# CPU_Dev_revB_2.net
KiCad netlist of a schematic drawn in EAGLE
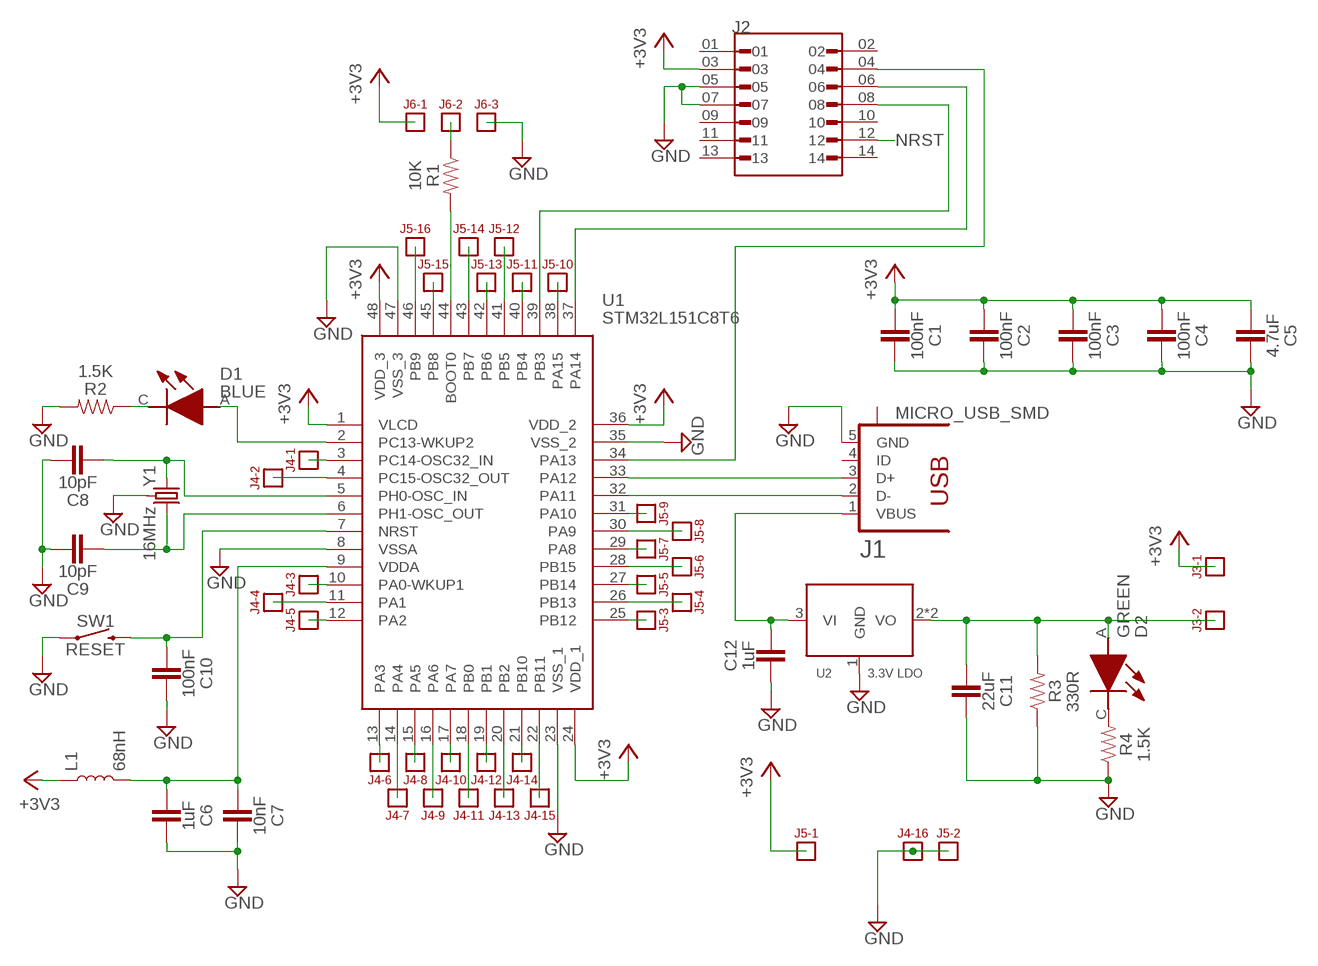
[diagram p0: schematic, sheet 1]

(export (version "E")
  (design (tool "Eeschema 10.0.6"))
  (components
    (comp (ref "C1")
      (value "100nF")
      (footprint "eagle-import:0402")
      (libsource (lib "eagle-import") (part "C_0402"))
    )
    (comp (ref "C2")
      (value "100nF")
      (footprint "eagle-import:0402")
      (libsource (lib "eagle-import") (part "C_0402"))
    )
    (comp (ref "C3")
      (value "100nF")
      (footprint "eagle-import:0402")
      (libsource (lib "eagle-import") (part "C_0402"))
    )
    (comp (ref "C4")
      (value "100nF")
      (footprint "eagle-import:0402")
      (libsource (lib "eagle-import") (part "C_0402"))
    )
    (comp (ref "C5")
      (value "4.7uF")
      (footprint "eagle-import:0402")
      (libsource (lib "eagle-import") (part "C_0402"))
    )
    (comp (ref "C6")
      (value "1uF")
      (footprint "eagle-import:0402")
      (libsource (lib "eagle-import") (part "C_0402"))
    )
    (comp (ref "C7")
      (value "10nF")
      (footprint "eagle-import:0402")
      (libsource (lib "eagle-import") (part "C_0402"))
    )
    (comp (ref "C8")
      (value "10pF")
      (footprint "eagle-import:0402")
      (libsource (lib "eagle-import") (part "C_0402"))
    )
    (comp (ref "C9")
      (value "10pF")
      (footprint "eagle-import:0402")
      (libsource (lib "eagle-import") (part "C_0402"))
    )
    (comp (ref "C10")
      (value "100nF")
      (footprint "eagle-import:0402")
      (libsource (lib "eagle-import") (part "C_0402"))
    )
    (comp (ref "C11")
      (value "22uF")
      (footprint "eagle-import:1206")
      (libsource (lib "eagle-import") (part "C_1206"))
    )
    (comp (ref "C12")
      (value "1uF")
      (footprint "eagle-import:0402")
      (libsource (lib "eagle-import") (part "C_0402"))
    )
    (comp (ref "D1")
      (value "BLUE")
      (footprint "eagle-import:LED_0603")
      (libsource (lib "eagle-import") (part "LED_0603"))
    )
    (comp (ref "D2")
      (value "GREEN")
      (footprint "eagle-import:LED_0603")
      (libsource (lib "eagle-import") (part "LED_0603"))
    )
    (comp (ref "J1")
      (value "MICRO_USB_SMD")
      (footprint "eagle-import:10118192-0002LF")
      (libsource (lib "eagle-import") (part "MICRO_USB_SMD"))
    )
    (comp (ref "J2")
      (value "HEADER_DEBUG_SMD")
      (footprint "eagle-import:HEADER_DEBUG_SMD")
      (libsource (lib "eagle-import") (part "HEADER_DEBUG_SMD"))
    )
    (comp (ref "J3")
      (value "HEADER_2PIN")
      (footprint "eagle-import:HEADER_2PIN")
      (libsource (lib "eagle-import") (part "HEADER_2PIN"))
    )
    (comp (ref "J4")
      (value "HEADER_16PIN")
      (footprint "eagle-import:HEADER_16PIN")
      (libsource (lib "eagle-import") (part "HEADER_16PIN"))
    )
    (comp (ref "J5")
      (value "HEADER_16PIN")
      (footprint "eagle-import:HEADER_16PIN")
      (libsource (lib "eagle-import") (part "HEADER_16PIN"))
    )
    (comp (ref "J6")
      (value "HEADER_3PIN")
      (footprint "eagle-import:HEADER_3PIN")
      (libsource (lib "eagle-import") (part "HEADER_3PIN"))
    )
    (comp (ref "L1")
      (value "68nH")
      (footprint "eagle-import:0603")
      (libsource (lib "eagle-import") (part "L_0603"))
    )
    (comp (ref "R1")
      (value "10K")
      (footprint "eagle-import:0402")
      (libsource (lib "eagle-import") (part "R_0402"))
    )
    (comp (ref "R2")
      (value "1.5K")
      (footprint "eagle-import:0402")
      (libsource (lib "eagle-import") (part "R_0402"))
    )
    (comp (ref "R3")
      (value "330R")
      (footprint "eagle-import:0402")
      (libsource (lib "eagle-import") (part "R_0402"))
    )
    (comp (ref "R4")
      (value "1.5K")
      (footprint "eagle-import:0402")
      (libsource (lib "eagle-import") (part "R_0402"))
    )
    (comp (ref "SW1")
      (value "RESET")
      (footprint "eagle-import:PUSHBUTTON_SMD")
      (libsource (lib "eagle-import") (part "PUSHBUTTON_SMD"))
    )
    (comp (ref "U1")
      (value "STM32L151C8T6")
      (footprint "eagle-import:LQFP-48_7X7")
      (fields (field (name "MOUSER_PART_NUMBER") "511-STM32L151C8T6"))
      (libsource (lib "eagle-import") (part "STM32L151C8T6"))
    )
    (comp (ref "U2")
      (value "3.3V LDO")
      (footprint "eagle-import:SOT223")
      (libsource (lib "eagle-import") (part "VREG_SOT223"))
    )
    (comp (ref "Y1")
      (value "16MHz")
      (footprint "eagle-import:SMD3225-4P")
      (libsource (lib "eagle-import") (part "XTAL_SMD3225-4P"))
    )
  )
  (nets
    (net (code "1") (name "+3V3") (class "Default")
      (node (ref "C1") (pin "1") (pinfunction "1_1") (pintype "passive"))
      (node (ref "C2") (pin "1") (pinfunction "1_1") (pintype "passive"))
      (node (ref "C3") (pin "1") (pinfunction "1_1") (pintype "passive"))
      (node (ref "C4") (pin "1") (pinfunction "1_1") (pintype "passive"))
      (node (ref "C5") (pin "1") (pinfunction "1_1") (pintype "passive"))
      (node (ref "J2") (pin "03") (pinfunction "03_03") (pintype "passive"))
      (node (ref "J3") (pin "P$1") (pinfunction "P$1_P$1") (pintype "bidirectional"))
      (node (ref "J5") (pin "P$1") (pinfunction "P$1_P$1") (pintype "bidirectional"))
      (node (ref "J6") (pin "P$1") (pinfunction "P$1_P$1") (pintype "bidirectional"))
      (node (ref "L1") (pin "1") (pinfunction "1_1") (pintype "passive"))
      (node (ref "U1") (pin "1") (pinfunction "VLCD_1") (pintype "bidirectional"))
      (node (ref "U1") (pin "24") (pinfunction "VDD_1_24") (pintype "bidirectional"))
      (node (ref "U1") (pin "36") (pinfunction "VDD_2_36") (pintype "bidirectional"))
      (node (ref "U1") (pin "48") (pinfunction "VDD_3_48") (pintype "bidirectional"))
    )
    (net (code "2") (name "/NRST") (class "Default")
      (node (ref "C10") (pin "1") (pinfunction "1_1") (pintype "passive"))
      (node (ref "J2") (pin "12") (pinfunction "12_12") (pintype "passive"))
      (node (ref "SW1") (pin "C1") (pinfunction "2_C1") (pintype "passive"))
      (node (ref "SW1") (pin "D1") (pinfunction "2_D1") (pintype "passive"))
      (node (ref "U1") (pin "7") (pinfunction "NRST_7") (pintype "bidirectional"))
    )
    (net (code "3") (name "GND") (class "Default")
      (node (ref "C1") (pin "2") (pinfunction "2_2") (pintype "passive"))
      (node (ref "C10") (pin "2") (pinfunction "2_2") (pintype "passive"))
      (node (ref "C11") (pin "2") (pinfunction "2_2") (pintype "passive"))
      (node (ref "C12") (pin "1") (pinfunction "1_1") (pintype "passive"))
      (node (ref "C2") (pin "2") (pinfunction "2_2") (pintype "passive"))
      (node (ref "C3") (pin "2") (pinfunction "2_2") (pintype "passive"))
      (node (ref "C4") (pin "2") (pinfunction "2_2") (pintype "passive"))
      (node (ref "C5") (pin "2") (pinfunction "2_2") (pintype "passive"))
      (node (ref "C6") (pin "2") (pinfunction "2_2") (pintype "passive"))
      (node (ref "C7") (pin "2") (pinfunction "2_2") (pintype "passive"))
      (node (ref "C8") (pin "2") (pinfunction "2_2") (pintype "passive"))
      (node (ref "C9") (pin "2") (pinfunction "2_2") (pintype "passive"))
      (node (ref "J1") (pin "5") (pinfunction "GND_5") (pintype "passive"))
      (node (ref "J2") (pin "05") (pinfunction "05_05") (pintype "passive"))
      (node (ref "J2") (pin "07") (pinfunction "07_07") (pintype "passive"))
      (node (ref "J4") (pin "P$16") (pinfunction "P$1_P$16") (pintype "bidirectional"))
      (node (ref "J5") (pin "P$2") (pinfunction "P$1_P$2") (pintype "bidirectional"))
      (node (ref "J6") (pin "P$3") (pinfunction "P$1_P$3") (pintype "bidirectional"))
      (node (ref "R2") (pin "2") (pinfunction "2_2") (pintype "passive"))
      (node (ref "R3") (pin "1") (pinfunction "1_1") (pintype "passive"))
      (node (ref "R4") (pin "1") (pinfunction "1_1") (pintype "passive"))
      (node (ref "SW1") (pin "A1") (pinfunction "1_A1") (pintype "passive"))
      (node (ref "SW1") (pin "B1") (pinfunction "1_B1") (pintype "passive"))
      (node (ref "U1") (pin "23") (pinfunction "VSS_1_23") (pintype "bidirectional"))
      (node (ref "U1") (pin "35") (pinfunction "VSS_2_35") (pintype "bidirectional"))
      (node (ref "U1") (pin "47") (pinfunction "VSS_3_47") (pintype "bidirectional"))
      (node (ref "U1") (pin "8") (pinfunction "VSSA_8") (pintype "bidirectional"))
      (node (ref "U2") (pin "1") (pinfunction "GND_1") (pintype "bidirectional"))
      (node (ref "Y1") (pin "2") (pinfunction "3_2") (pintype "passive"))
      (node (ref "Y1") (pin "4") (pinfunction "3_4") (pintype "passive"))
    )
    (net (code "4") (name "Net-(D1-K)") (class "Default")
      (node (ref "D1") (pin "C") (pinfunction "K_C") (pintype "bidirectional"))
      (node (ref "R2") (pin "1") (pinfunction "1_1") (pintype "passive"))
    )
    (net (code "5") (name "Net-(D2-K)") (class "Default")
      (node (ref "D2") (pin "C") (pinfunction "K_C") (pintype "bidirectional"))
      (node (ref "R4") (pin "2") (pinfunction "2_2") (pintype "passive"))
    )
    (net (code "6") (name "Net-(J1-D+)") (class "Default")
      (node (ref "J1") (pin "3") (pinfunction "D+_3") (pintype "passive"))
      (node (ref "U1") (pin "33") (pinfunction "PA12_33") (pintype "bidirectional"))
    )
    (net (code "7") (name "Net-(J1-D-)") (class "Default")
      (node (ref "J1") (pin "2") (pinfunction "D-_2") (pintype "passive"))
      (node (ref "U1") (pin "32") (pinfunction "PA11_32") (pintype "bidirectional"))
    )
    (net (code "8") (name "Net-(J1-VBUS)") (class "Default")
      (node (ref "C12") (pin "2") (pinfunction "2_2") (pintype "passive"))
      (node (ref "J1") (pin "1") (pinfunction "VBUS_1") (pintype "passive"))
      (node (ref "U2") (pin "3") (pinfunction "VI_3") (pintype "bidirectional"))
    )
    (net (code "9") (name "Net-(J3B-P$1)") (class "Default")
      (node (ref "C11") (pin "1") (pinfunction "1_1") (pintype "passive"))
      (node (ref "D2") (pin "A") (pinfunction "A_A") (pintype "bidirectional"))
      (node (ref "J3") (pin "P$2") (pinfunction "P$1_P$2") (pintype "bidirectional"))
      (node (ref "R3") (pin "2") (pinfunction "2_2") (pintype "passive"))
      (node (ref "U2") (pin "2") (pinfunction "VO_2") (pintype "bidirectional"))
      (node (ref "U2") (pin "4") (pinfunction "VO_4") (pintype "bidirectional"))
    )
    (net (code "10") (name "Net-(J4B-P$1)") (class "Default")
      (node (ref "J4") (pin "P$10") (pinfunction "P$1_P$10") (pintype "bidirectional"))
      (node (ref "U1") (pin "17") (pinfunction "PA7_17") (pintype "bidirectional"))
    )
    (net (code "11") (name "Net-(J4C-P$1)") (class "Default")
      (node (ref "J4") (pin "P$11") (pinfunction "P$1_P$11") (pintype "bidirectional"))
      (node (ref "U1") (pin "18") (pinfunction "PB0_18") (pintype "bidirectional"))
    )
    (net (code "12") (name "Net-(J4D-P$1)") (class "Default")
      (node (ref "J4") (pin "P$12") (pinfunction "P$1_P$12") (pintype "bidirectional"))
      (node (ref "U1") (pin "19") (pinfunction "PB1_19") (pintype "bidirectional"))
    )
    (net (code "13") (name "Net-(J4E-P$1)") (class "Default")
      (node (ref "J4") (pin "P$13") (pinfunction "P$1_P$13") (pintype "bidirectional"))
      (node (ref "U1") (pin "20") (pinfunction "PB2_20") (pintype "bidirectional"))
    )
    (net (code "14") (name "Net-(J4F-P$1)") (class "Default")
      (node (ref "J4") (pin "P$14") (pinfunction "P$1_P$14") (pintype "bidirectional"))
      (node (ref "U1") (pin "21") (pinfunction "PB10_21") (pintype "bidirectional"))
    )
    (net (code "15") (name "Net-(J4G-P$1)") (class "Default")
      (node (ref "J4") (pin "P$15") (pinfunction "P$1_P$15") (pintype "bidirectional"))
      (node (ref "U1") (pin "22") (pinfunction "PB11_22") (pintype "bidirectional"))
    )
    (net (code "16") (name "Net-(J4I-P$1)") (class "Default")
      (node (ref "J4") (pin "P$2") (pinfunction "P$1_P$2") (pintype "bidirectional"))
      (node (ref "U1") (pin "4") (pinfunction "PC15-OSC32_OUT_4") (pintype "bidirectional"))
    )
    (net (code "17") (name "Net-(J4J-P$1)") (class "Default")
      (node (ref "J4") (pin "P$3") (pinfunction "P$1_P$3") (pintype "bidirectional"))
      (node (ref "U1") (pin "10") (pinfunction "PA0-WKUP1_10") (pintype "bidirectional"))
    )
    (net (code "18") (name "Net-(J4K-P$1)") (class "Default")
      (node (ref "J4") (pin "P$4") (pinfunction "P$1_P$4") (pintype "bidirectional"))
      (node (ref "U1") (pin "11") (pinfunction "PA1_11") (pintype "bidirectional"))
    )
    (net (code "19") (name "Net-(J4L-P$1)") (class "Default")
      (node (ref "J4") (pin "P$5") (pinfunction "P$1_P$5") (pintype "bidirectional"))
      (node (ref "U1") (pin "12") (pinfunction "PA2_12") (pintype "bidirectional"))
    )
    (net (code "20") (name "Net-(J4M-P$1)") (class "Default")
      (node (ref "J4") (pin "P$6") (pinfunction "P$1_P$6") (pintype "bidirectional"))
      (node (ref "U1") (pin "13") (pinfunction "PA3_13") (pintype "bidirectional"))
    )
    (net (code "21") (name "Net-(J4N-P$1)") (class "Default")
      (node (ref "J4") (pin "P$7") (pinfunction "P$1_P$7") (pintype "bidirectional"))
      (node (ref "U1") (pin "14") (pinfunction "PA4_14") (pintype "bidirectional"))
    )
    (net (code "22") (name "Net-(J4O-P$1)") (class "Default")
      (node (ref "J4") (pin "P$8") (pinfunction "P$1_P$8") (pintype "bidirectional"))
      (node (ref "U1") (pin "15") (pinfunction "PA5_15") (pintype "bidirectional"))
    )
    (net (code "23") (name "Net-(J4P-P$1)") (class "Default")
      (node (ref "J4") (pin "P$9") (pinfunction "P$1_P$9") (pintype "bidirectional"))
      (node (ref "U1") (pin "16") (pinfunction "PA6_16") (pintype "bidirectional"))
    )
    (net (code "24") (name "Net-(J5B-P$1)") (class "Default")
      (node (ref "J5") (pin "P$10") (pinfunction "P$1_P$10") (pintype "bidirectional"))
      (node (ref "U1") (pin "38") (pinfunction "PA15_38") (pintype "bidirectional"))
    )
    (net (code "25") (name "Net-(J5C-P$1)") (class "Default")
      (node (ref "J5") (pin "P$11") (pinfunction "P$1_P$11") (pintype "bidirectional"))
      (node (ref "U1") (pin "40") (pinfunction "PB4_40") (pintype "bidirectional"))
    )
    (net (code "26") (name "Net-(J5D-P$1)") (class "Default")
      (node (ref "J5") (pin "P$12") (pinfunction "P$1_P$12") (pintype "bidirectional"))
      (node (ref "U1") (pin "41") (pinfunction "PB5_41") (pintype "bidirectional"))
    )
    (net (code "27") (name "Net-(J5E-P$1)") (class "Default")
      (node (ref "J5") (pin "P$13") (pinfunction "P$1_P$13") (pintype "bidirectional"))
      (node (ref "U1") (pin "42") (pinfunction "PB6_42") (pintype "bidirectional"))
    )
    (net (code "28") (name "Net-(J5F-P$1)") (class "Default")
      (node (ref "J5") (pin "P$14") (pinfunction "P$1_P$14") (pintype "bidirectional"))
      (node (ref "U1") (pin "43") (pinfunction "PB7_43") (pintype "bidirectional"))
    )
    (net (code "29") (name "Net-(J5G-P$1)") (class "Default")
      (node (ref "J5") (pin "P$15") (pinfunction "P$1_P$15") (pintype "bidirectional"))
      (node (ref "U1") (pin "45") (pinfunction "PB8_45") (pintype "bidirectional"))
    )
    (net (code "30") (name "Net-(J5H-P$1)") (class "Default")
      (node (ref "J5") (pin "P$16") (pinfunction "P$1_P$16") (pintype "bidirectional"))
      (node (ref "U1") (pin "46") (pinfunction "PB9_46") (pintype "bidirectional"))
    )
    (net (code "31") (name "Net-(J5J-P$1)") (class "Default")
      (node (ref "J5") (pin "P$3") (pinfunction "P$1_P$3") (pintype "bidirectional"))
      (node (ref "U1") (pin "25") (pinfunction "PB12_25") (pintype "bidirectional"))
    )
    (net (code "32") (name "Net-(J5K-P$1)") (class "Default")
      (node (ref "J5") (pin "P$4") (pinfunction "P$1_P$4") (pintype "bidirectional"))
      (node (ref "U1") (pin "26") (pinfunction "PB13_26") (pintype "bidirectional"))
    )
    (net (code "33") (name "Net-(J5L-P$1)") (class "Default")
      (node (ref "J5") (pin "P$5") (pinfunction "P$1_P$5") (pintype "bidirectional"))
      (node (ref "U1") (pin "27") (pinfunction "PB14_27") (pintype "bidirectional"))
    )
    (net (code "34") (name "Net-(J5M-P$1)") (class "Default")
      (node (ref "J5") (pin "P$6") (pinfunction "P$1_P$6") (pintype "bidirectional"))
      (node (ref "U1") (pin "28") (pinfunction "PB15_28") (pintype "bidirectional"))
    )
    (net (code "35") (name "Net-(J5N-P$1)") (class "Default")
      (node (ref "J5") (pin "P$7") (pinfunction "P$1_P$7") (pintype "bidirectional"))
      (node (ref "U1") (pin "29") (pinfunction "PA8_29") (pintype "bidirectional"))
    )
    (net (code "36") (name "Net-(J5O-P$1)") (class "Default")
      (node (ref "J5") (pin "P$8") (pinfunction "P$1_P$8") (pintype "bidirectional"))
      (node (ref "U1") (pin "30") (pinfunction "PA9_30") (pintype "bidirectional"))
    )
    (net (code "37") (name "Net-(J5P-P$1)") (class "Default")
      (node (ref "J5") (pin "P$9") (pinfunction "P$1_P$9") (pintype "bidirectional"))
      (node (ref "U1") (pin "31") (pinfunction "PA10_31") (pintype "bidirectional"))
    )
    (net (code "38") (name "Net-(J6B-P$1)") (class "Default")
      (node (ref "J6") (pin "P$2") (pinfunction "P$1_P$2") (pintype "bidirectional"))
      (node (ref "R1") (pin "1") (pinfunction "1_1") (pintype "passive"))
    )
    (net (code "39") (name "Net-(U1-BOOT0)") (class "Default")
      (node (ref "R1") (pin "2") (pinfunction "2_2") (pintype "passive"))
      (node (ref "U1") (pin "44") (pinfunction "BOOT0_44") (pintype "bidirectional"))
    )
    (net (code "40") (name "Net-(U1-PA13)") (class "Default")
      (node (ref "J2") (pin "04") (pinfunction "04_04") (pintype "passive"))
      (node (ref "U1") (pin "34") (pinfunction "PA13_34") (pintype "bidirectional"))
    )
    (net (code "41") (name "Net-(U1-PA14)") (class "Default")
      (node (ref "J2") (pin "06") (pinfunction "06_06") (pintype "passive"))
      (node (ref "U1") (pin "37") (pinfunction "PA14_37") (pintype "bidirectional"))
    )
    (net (code "42") (name "Net-(U1-PB3)") (class "Default")
      (node (ref "J2") (pin "08") (pinfunction "08_08") (pintype "passive"))
      (node (ref "U1") (pin "39") (pinfunction "PB3_39") (pintype "bidirectional"))
    )
    (net (code "43") (name "Net-(U1-PC13-WKUP2)") (class "Default")
      (node (ref "D1") (pin "A") (pinfunction "A_A") (pintype "bidirectional"))
      (node (ref "U1") (pin "2") (pinfunction "PC13-WKUP2_2") (pintype "bidirectional"))
    )
    (net (code "44") (name "Net-(U1-PC14-OSC32_IN)") (class "Default")
      (node (ref "J4") (pin "P$1") (pinfunction "P$1_P$1") (pintype "bidirectional"))
      (node (ref "U1") (pin "3") (pinfunction "PC14-OSC32_IN_3") (pintype "bidirectional"))
    )
    (net (code "45") (name "Net-(U1-PH0-OSC_IN)") (class "Default")
      (node (ref "C8") (pin "1") (pinfunction "1_1") (pintype "passive"))
      (node (ref "U1") (pin "5") (pinfunction "PH0-OSC_IN_5") (pintype "bidirectional"))
      (node (ref "Y1") (pin "1") (pinfunction "1_1") (pintype "passive"))
    )
    (net (code "46") (name "Net-(U1-PH1-OSC_OUT)") (class "Default")
      (node (ref "C9") (pin "1") (pinfunction "1_1") (pintype "passive"))
      (node (ref "U1") (pin "6") (pinfunction "PH1-OSC_OUT_6") (pintype "bidirectional"))
      (node (ref "Y1") (pin "3") (pinfunction "2_3") (pintype "passive"))
    )
    (net (code "47") (name "Net-(U1-VDDA)") (class "Default")
      (node (ref "C6") (pin "1") (pinfunction "1_1") (pintype "passive"))
      (node (ref "C7") (pin "1") (pinfunction "1_1") (pintype "passive"))
      (node (ref "L1") (pin "2") (pinfunction "2_2") (pintype "passive"))
      (node (ref "U1") (pin "9") (pinfunction "VDDA_9") (pintype "bidirectional"))
    )
    (net (code "48") (name "unconnected-(J1-ID-Pad4)") (class "Default")
      (node (ref "J1") (pin "4") (pinfunction "ID_4") (pintype "passive"))
    )
    (net (code "49") (name "unconnected-(J1-PadS1)") (class "Default")
      (node (ref "J1") (pin "S1") (pinfunction "S1_S1") (pintype "passive"))
    )
    (net (code "50") (name "unconnected-(J2-Pad01)") (class "Default")
      (node (ref "J2") (pin "01") (pinfunction "01_01") (pintype "passive"))
    )
    (net (code "51") (name "unconnected-(J2-Pad02)") (class "Default")
      (node (ref "J2") (pin "02") (pinfunction "02_02") (pintype "passive"))
    )
    (net (code "52") (name "unconnected-(J2-Pad09)") (class "Default")
      (node (ref "J2") (pin "09") (pinfunction "09_09") (pintype "passive"))
    )
    (net (code "53") (name "unconnected-(J2-Pad10)") (class "Default")
      (node (ref "J2") (pin "10") (pinfunction "10_10") (pintype "passive"))
    )
    (net (code "54") (name "unconnected-(J2-Pad11)") (class "Default")
      (node (ref "J2") (pin "11") (pinfunction "11_11") (pintype "passive"))
    )
    (net (code "55") (name "unconnected-(J2-Pad13)") (class "Default")
      (node (ref "J2") (pin "13") (pinfunction "13_13") (pintype "passive"))
    )
    (net (code "56") (name "unconnected-(J2-Pad14)") (class "Default")
      (node (ref "J2") (pin "14") (pinfunction "14_14") (pintype "passive"))
    )
  )
)
